# Sheet2.net
KiCad netlist of a schematic drawn in Altium Designer
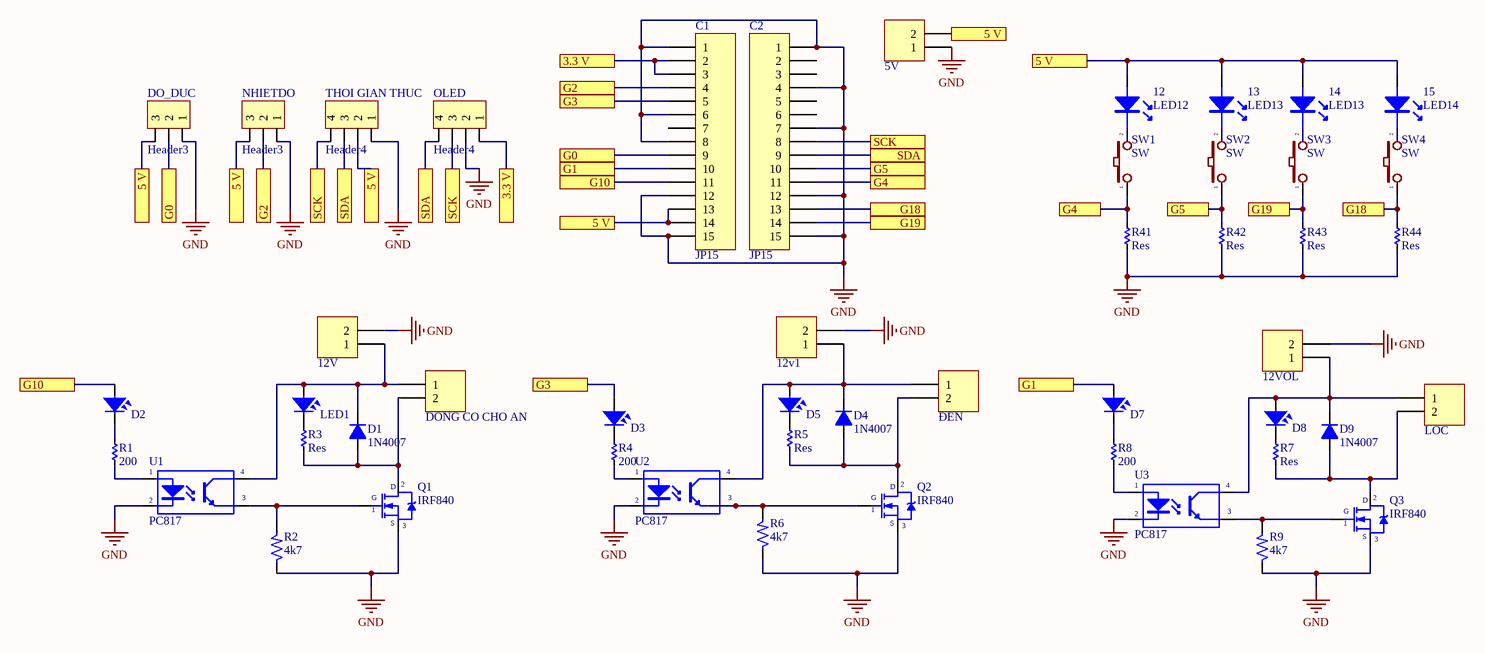
[diagram p0: Sheet2.SchDoc]

(export (version "E")
  (design (tool "Eeschema 10.0.6"))
  (components
    (comp (ref "5V")
      (value "Header 2_1")
      (footprint "HED2")
      (description "Header, 2-Pin")
      (fields (field (name "MANUFACTURER") "Generic Components"))
      (libsource (lib "syhaunguyen__1") (part "Header 2_1"))
    )
    (comp (ref "12") (value "LED12") (footprint "CAP10UF") (libsource (lib "minhha") (part "LED")))
    (comp (ref "12V")
      (value "Header 2_1")
      (footprint "HED2")
      (description "Header, 2-Pin")
      (fields (field (name "MANUFACTURER") "Generic Components"))
      (libsource (lib "syhaunguyen__1") (part "Header 2_1"))
    )
    (comp (ref "12v1")
      (value "Header 2_1")
      (footprint "HED2")
      (description "Header, 2-Pin")
      (fields (field (name "MANUFACTURER") "Generic Components"))
      (libsource (lib "syhaunguyen__1") (part "Header 2_1"))
    )
    (comp (ref "12VOL")
      (value "Header 2_1")
      (footprint "HED2")
      (description "Header, 2-Pin")
      (fields (field (name "MANUFACTURER") "Generic Components"))
      (libsource (lib "syhaunguyen__1") (part "Header 2_1"))
    )
    (comp (ref "13") (value "LED13") (footprint "CAP10UF") (libsource (lib "minhha") (part "LED")))
    (comp (ref "14") (value "LED13") (footprint "CAP10UF") (libsource (lib "minhha") (part "LED")))
    (comp (ref "15") (value "LED14") (footprint "CAP10UF") (libsource (lib "minhha") (part "LED")))
    (comp (ref "C1")
      (value "JP15")
      (footprint "JP15-C1T")
      (description "WR-PHD 2.54 mm Angled Socket Header")
      (fields
        (field (name "MANUFACTURER") "Würth Elektronik eiSos GmbH")
        (field (name "PARTNO") "613015143121")
        (field (name "CREATED BY") "Karrer Zheng")
      )
      (libsource (lib "") (part "JP15_1"))
    )
    (comp (ref "C2")
      (value "JP15")
      (footprint "JP15-C1T")
      (description "WR-PHD 2.54 mm Angled Socket Header")
      (fields
        (field (name "MANUFACTURER") "Würth Elektronik eiSos GmbH")
        (field (name "PARTNO") "613015143121")
        (field (name "CREATED BY") "Karrer Zheng")
      )
      (libsource (lib "Library1") (part "JP15"))
    )
    (comp (ref "D1")
      (value "1N4007")
      (footprint "D1A")
      (description "Diode 1A")
      (libsource (lib "minhha") (part "D1A"))
    )
    (comp (ref "D2")
      (value "LED")
      (footprint "LED-3")
      (description "LED Single colour Green and Red")
      (libsource (lib "Altium_Devzone") (part "LED"))
    )
    (comp (ref "D3")
      (value "LED")
      (footprint "LED-3")
      (description "LED Single colour Green and Red")
      (libsource (lib "Altium_Devzone") (part "LED"))
    )
    (comp (ref "D4")
      (value "1N4007")
      (footprint "D1A")
      (description "Diode 1A")
      (libsource (lib "minhha") (part "D1A"))
    )
    (comp (ref "D5")
      (value "LED")
      (footprint "LED-3MM-YELLOW")
      (description "LED Single colour Green and Red")
      (libsource (lib "Library1") (part "LED"))
    )
    (comp (ref "D7")
      (value "LED")
      (footprint "LED-3")
      (description "LED Single colour Green and Red")
      (libsource (lib "Altium_Devzone") (part "LED"))
    )
    (comp (ref "D8")
      (value "LED")
      (footprint "LED-3MM-YELLOW")
      (description "LED Single colour Green and Red")
      (libsource (lib "Library1") (part "LED"))
    )
    (comp (ref "D9")
      (value "1N4007")
      (footprint "D1A")
      (description "Diode 1A")
      (libsource (lib "minhha") (part "D1A"))
    )
    (comp (ref "DONG CO CHO AN")
      (value "Header 2_1")
      (footprint "HED2")
      (description "Header, 2-Pin")
      (fields (field (name "MANUFACTURER") "Generic Components"))
      (libsource (lib "") (part "Header 2_1_1"))
    )
    (comp (ref "DO_DUC")
      (value "Header3")
      (footprint "Header3")
      (description "Header IDC, 3 x 1 Pin Vertical 2.54mm Pitch (Non-Boxed, Male)")
      (fields
        (field (name "MANUFACTURER") "Würth Elektronik eiSos GmbH")
        (field (name "PARTNO") "613002143121")
        (field (name "CREATED BY") "Karrer Zheng")
      )
      (libsource (lib "Library1") (part "Header3"))
    )
    (comp (ref "LED1")
      (value "LED")
      (footprint "LED-3MM-YELLOW")
      (description "LED Single colour Green and Red")
      (libsource (lib "Library1") (part "LED"))
    )
    (comp (ref "LOC")
      (value "Header 2_1")
      (footprint "HED2")
      (description "Header, 2-Pin")
      (fields (field (name "MANUFACTURER") "Generic Components"))
      (libsource (lib "") (part "Header 2_1_1"))
    )
    (comp (ref "NHIETDO")
      (value "Header3")
      (footprint "Header3")
      (description "Header IDC, 3 x 1 Pin Vertical 2.54mm Pitch (Non-Boxed, Male)")
      (fields
        (field (name "MANUFACTURER") "Würth Elektronik eiSos GmbH")
        (field (name "PARTNO") "613002143121")
        (field (name "CREATED BY") "Karrer Zheng")
      )
      (libsource (lib "Library1") (part "Header3"))
    )
    (comp (ref "OLED")
      (value "Header4")
      (footprint "Header4")
      (description "Header IDC, 4 x 1 Pin Vertical 2.54mm Pitch (Non-Boxed, Male)")
      (fields
        (field (name "MANUFACTURER") "Würth Elektronik eiSos GmbH")
        (field (name "PARTNO") "613002143121")
        (field (name "CREATED BY") "Karrer Zheng")
      )
      (libsource (lib "Library1") (part "Header4"))
    )
    (comp (ref "Q1")
      (value "IRF840")
      (footprint "TO220H1")
      (description "MOSFET N - CHANNEL 500V - 0.75 - 8A - TO-220")
      (libsource (lib "Library1") (part "IRF840"))
    )
    (comp (ref "Q2")
      (value "IRF840")
      (footprint "TO220H1")
      (description "MOSFET N - CHANNEL 500V - 0.75 - 8A - TO-220")
      (libsource (lib "Library1") (part "IRF840"))
    )
    (comp (ref "Q3")
      (value "IRF840")
      (footprint "TO220H1")
      (description "MOSFET N - CHANNEL 500V - 0.75 - 8A - TO-220")
      (libsource (lib "Library1") (part "IRF840"))
    )
    (comp (ref "R1")
      (value "200")
      (footprint "RES-1/2W")
      (description "Res")
      (fields
        (field (name "MANUFACTURER") "Generic Components")
        (field (name "PUBLISHER") "Altium Hobart Technology Centre")
      )
      (libsource (lib "Library1") (part "Res"))
    )
    (comp (ref "R2")
      (value "4k7")
      (footprint "DIEN TRO 1/4 W")
      (description "Resistor 1/4W")
      (libsource (lib "minhha") (part "Res"))
    )
    (comp (ref "R3")
      (value "Res")
      (footprint "RES-1/2W")
      (fields
        (field (name "MANUFACTURER") "Generic Components")
        (field (name "PUBLISHER") "Altium Hobart Technology Centre")
      )
      (libsource (lib "Library1") (part "Res"))
    )
    (comp (ref "R4")
      (value "200")
      (footprint "RES-1/2W")
      (description "Res")
      (fields
        (field (name "MANUFACTURER") "Generic Components")
        (field (name "PUBLISHER") "Altium Hobart Technology Centre")
      )
      (libsource (lib "Library1") (part "Res"))
    )
    (comp (ref "R5")
      (value "Res")
      (footprint "RES-1/2W")
      (fields
        (field (name "MANUFACTURER") "Generic Components")
        (field (name "PUBLISHER") "Altium Hobart Technology Centre")
      )
      (libsource (lib "Library1") (part "Res"))
    )
    (comp (ref "R6")
      (value "4k7")
      (footprint "DIEN TRO 1/4 W")
      (description "Resistor 1/4W")
      (libsource (lib "minhha") (part "Res"))
    )
    (comp (ref "R7")
      (value "Res")
      (footprint "RES-1/2W")
      (fields
        (field (name "MANUFACTURER") "Generic Components")
        (field (name "PUBLISHER") "Altium Hobart Technology Centre")
      )
      (libsource (lib "Library1") (part "Res"))
    )
    (comp (ref "R8")
      (value "200")
      (footprint "RES-1/2W")
      (description "Res")
      (fields
        (field (name "MANUFACTURER") "Generic Components")
        (field (name "PUBLISHER") "Altium Hobart Technology Centre")
      )
      (libsource (lib "Library1") (part "Res"))
    )
    (comp (ref "R9")
      (value "4k7")
      (footprint "DIEN TRO 1/4 W")
      (description "Resistor 1/4W")
      (libsource (lib "minhha") (part "Res"))
    )
    (comp (ref "R41")
      (value "Res")
      (footprint "RES-1/2W")
      (fields
        (field (name "MANUFACTURER") "Generic Components")
        (field (name "PUBLISHER") "Altium Hobart Technology Centre")
      )
      (libsource (lib "Library1") (part "Res"))
    )
    (comp (ref "R42")
      (value "Res")
      (footprint "RES-1/2W")
      (fields
        (field (name "MANUFACTURER") "Generic Components")
        (field (name "PUBLISHER") "Altium Hobart Technology Centre")
      )
      (libsource (lib "Library1") (part "Res"))
    )
    (comp (ref "R43")
      (value "Res")
      (footprint "RES-1/2W")
      (fields
        (field (name "MANUFACTURER") "Generic Components")
        (field (name "PUBLISHER") "Altium Hobart Technology Centre")
      )
      (libsource (lib "Library1") (part "Res"))
    )
    (comp (ref "R44")
      (value "Res")
      (footprint "RES-1/2W")
      (fields
        (field (name "MANUFACTURER") "Generic Components")
        (field (name "PUBLISHER") "Altium Hobart Technology Centre")
      )
      (libsource (lib "Library1") (part "Res"))
    )
    (comp (ref "SW1")
      (value "SW")
      (footprint "SW2")
      (description "Switch button 2 pin")
      (libsource (lib "syhaunguyen__1") (part "SW2"))
    )
    (comp (ref "SW2")
      (value "SW")
      (footprint "SW2")
      (description "Switch button 2 pin")
      (libsource (lib "syhaunguyen__1") (part "SW2"))
    )
    (comp (ref "SW3")
      (value "SW")
      (footprint "SW2")
      (description "Switch button 2 pin")
      (libsource (lib "syhaunguyen__1") (part "SW2"))
    )
    (comp (ref "SW4")
      (value "SW")
      (footprint "SW2")
      (description "Switch button 2 pin")
      (libsource (lib "syhaunguyen__1") (part "SW2"))
    )
    (comp (ref "THOI GIAN THUC")
      (value "Header4")
      (footprint "Header4")
      (description "Header IDC, 4 x 1 Pin Vertical 2.54mm Pitch (Non-Boxed, Male)")
      (fields
        (field (name "MANUFACTURER") "Würth Elektronik eiSos GmbH")
        (field (name "PARTNO") "613002143121")
        (field (name "CREATED BY") "Karrer Zheng")
      )
      (libsource (lib "Library1") (part "Header4"))
    )
    (comp (ref "U1")
      (value "PC817")
      (footprint "DIP4")
      (description "Single Opto")
      (libsource (lib "Library1") (part "PC817"))
    )
    (comp (ref "U2")
      (value "PC817")
      (footprint "DIP4")
      (description "Single Opto")
      (libsource (lib "Library1") (part "PC817"))
    )
    (comp (ref "U3")
      (value "PC817")
      (footprint "DIP4")
      (description "Single Opto")
      (libsource (lib "Library1") (part "PC817"))
    )
    (comp (ref "ĐEN")
      (value "Header 2_1")
      (footprint "HED2")
      (description "Header, 2-Pin")
      (fields (field (name "MANUFACTURER") "Generic Components"))
      (libsource (lib "") (part "Header 2_1_1"))
    )
  )
  (nets
    (net (code "1") (name "/3.3 V") (class "Default")
      (node (ref "C1") (pin "2") (pinfunction "2_2") (pintype "passive"))
      (node (ref "C1") (pin "3") (pinfunction "3_3") (pintype "passive"))
      (node (ref "OLED") (pin "1") (pinfunction "1_1") (pintype "passive"))
    )
    (net (code "2") (name "/5 V") (class "Default")
      (node (ref "12") (pin "1") (pinfunction "1_1") (pintype "passive"))
      (node (ref "13") (pin "1") (pinfunction "1_1") (pintype "passive"))
      (node (ref "14") (pin "1") (pinfunction "1_1") (pintype "passive"))
      (node (ref "15") (pin "1") (pinfunction "1_1") (pintype "passive"))
      (node (ref "5V") (pin "2") (pinfunction "2_2") (pintype "passive"))
      (node (ref "C1") (pin "13") (pinfunction "13_13") (pintype "passive"))
      (node (ref "C1") (pin "14") (pinfunction "14_14") (pintype "passive"))
      (node (ref "DO_DUC") (pin "3") (pinfunction "3_3") (pintype "passive"))
      (node (ref "NHIETDO") (pin "3") (pinfunction "3_3") (pintype "passive"))
      (node (ref "THOI GIAN THUC") (pin "2") (pinfunction "2_2") (pintype "passive"))
    )
    (net (code "3") (name "/G0") (class "Default")
      (node (ref "C1") (pin "9") (pinfunction "9_9") (pintype "passive"))
      (node (ref "DO_DUC") (pin "2") (pinfunction "2_2") (pintype "passive"))
    )
    (net (code "4") (name "/G1") (class "Default")
      (node (ref "C1") (pin "10") (pinfunction "10_10") (pintype "passive"))
      (node (ref "D7") (pin "1") (pinfunction "1_1") (pintype "passive"))
    )
    (net (code "5") (name "/G2") (class "Default")
      (node (ref "C1") (pin "4") (pinfunction "4_4") (pintype "passive"))
      (node (ref "NHIETDO") (pin "2") (pinfunction "2_2") (pintype "passive"))
    )
    (net (code "6") (name "/G3") (class "Default")
      (node (ref "C1") (pin "5") (pinfunction "5_5") (pintype "passive"))
      (node (ref "D3") (pin "1") (pinfunction "1_1") (pintype "passive"))
    )
    (net (code "7") (name "/G4") (class "Default")
      (node (ref "C2") (pin "11") (pinfunction "11_11") (pintype "passive"))
      (node (ref "R41") (pin "1") (pinfunction "1_1") (pintype "passive"))
      (node (ref "SW1") (pin "1") (pinfunction "1_1") (pintype "passive"))
    )
    (net (code "8") (name "/G5") (class "Default")
      (node (ref "C2") (pin "10") (pinfunction "10_10") (pintype "passive"))
      (node (ref "R42") (pin "1") (pinfunction "1_1") (pintype "passive"))
      (node (ref "SW2") (pin "1") (pinfunction "1_1") (pintype "passive"))
    )
    (net (code "9") (name "/G10") (class "Default")
      (node (ref "C1") (pin "11") (pinfunction "11_11") (pintype "passive"))
      (node (ref "D2") (pin "1") (pinfunction "1_1") (pintype "passive"))
    )
    (net (code "10") (name "/G18") (class "Default")
      (node (ref "C2") (pin "13") (pinfunction "13_13") (pintype "passive"))
      (node (ref "R44") (pin "1") (pinfunction "1_1") (pintype "passive"))
      (node (ref "SW4") (pin "1") (pinfunction "1_1") (pintype "passive"))
    )
    (net (code "11") (name "/G19") (class "Default")
      (node (ref "C2") (pin "14") (pinfunction "14_14") (pintype "passive"))
      (node (ref "R43") (pin "1") (pinfunction "1_1") (pintype "passive"))
      (node (ref "SW3") (pin "1") (pinfunction "1_1") (pintype "passive"))
    )
    (net (code "12") (name "/SCK") (class "Default")
      (node (ref "C2") (pin "8") (pinfunction "8_8") (pintype "passive"))
      (node (ref "OLED") (pin "3") (pinfunction "3_3") (pintype "passive"))
      (node (ref "THOI GIAN THUC") (pin "4") (pinfunction "4_4") (pintype "passive"))
    )
    (net (code "13") (name "/SDA") (class "Default")
      (node (ref "C2") (pin "9") (pinfunction "9_9") (pintype "passive"))
      (node (ref "OLED") (pin "4") (pinfunction "4_4") (pintype "passive"))
      (node (ref "THOI GIAN THUC") (pin "3") (pinfunction "3_3") (pintype "passive"))
    )
    (net (code "14") (name "GND") (class "Default")
      (node (ref "12V") (pin "2") (pinfunction "2_2") (pintype "passive"))
      (node (ref "12VOL") (pin "2") (pinfunction "2_2") (pintype "passive"))
      (node (ref "12v1") (pin "2") (pinfunction "2_2") (pintype "passive"))
      (node (ref "5V") (pin "1") (pinfunction "1_1") (pintype "passive"))
      (node (ref "C1") (pin "1") (pinfunction "1_1") (pintype "passive"))
      (node (ref "C1") (pin "12") (pinfunction "12_12") (pintype "passive"))
      (node (ref "C1") (pin "15") (pinfunction "15_15") (pintype "passive"))
      (node (ref "C1") (pin "6") (pinfunction "6_6") (pintype "passive"))
      (node (ref "C1") (pin "8") (pinfunction "8_8") (pintype "passive"))
      (node (ref "C2") (pin "1") (pinfunction "1_1") (pintype "passive"))
      (node (ref "C2") (pin "12") (pinfunction "12_12") (pintype "passive"))
      (node (ref "C2") (pin "15") (pinfunction "15_15") (pintype "passive"))
      (node (ref "C2") (pin "4") (pinfunction "4_4") (pintype "passive"))
      (node (ref "C2") (pin "7") (pinfunction "7_7") (pintype "passive"))
      (node (ref "DO_DUC") (pin "1") (pinfunction "1_1") (pintype "passive"))
      (node (ref "NHIETDO") (pin "1") (pinfunction "1_1") (pintype "passive"))
      (node (ref "OLED") (pin "2") (pinfunction "2_2") (pintype "passive"))
      (node (ref "Q1") (pin "3") (pinfunction "S_3") (pintype "passive"))
      (node (ref "Q2") (pin "3") (pinfunction "S_3") (pintype "passive"))
      (node (ref "Q3") (pin "3") (pinfunction "S_3") (pintype "passive"))
      (node (ref "R2") (pin "1") (pinfunction "1_1") (pintype "passive"))
      (node (ref "R41") (pin "2") (pinfunction "2_2") (pintype "passive"))
      (node (ref "R42") (pin "2") (pinfunction "2_2") (pintype "passive"))
      (node (ref "R43") (pin "2") (pinfunction "2_2") (pintype "passive"))
      (node (ref "R44") (pin "2") (pinfunction "2_2") (pintype "passive"))
      (node (ref "R6") (pin "1") (pinfunction "1_1") (pintype "passive"))
      (node (ref "R9") (pin "1") (pinfunction "1_1") (pintype "passive"))
      (node (ref "THOI GIAN THUC") (pin "1") (pinfunction "1_1") (pintype "passive"))
      (node (ref "U1") (pin "2") (pinfunction "K_2") (pintype "passive"))
      (node (ref "U2") (pin "2") (pinfunction "K_2") (pintype "passive"))
      (node (ref "U3") (pin "2") (pinfunction "K_2") (pintype "passive"))
    )
    (net (code "15") (name "Net-(12-Pad2)") (class "Default")
      (node (ref "12") (pin "2") (pinfunction "2_2") (pintype "passive"))
      (node (ref "SW1") (pin "2") (pinfunction "2_2") (pintype "passive"))
    )
    (net (code "16") (name "Net-(13-Pad2)") (class "Default")
      (node (ref "13") (pin "2") (pinfunction "2_2") (pintype "passive"))
      (node (ref "SW2") (pin "2") (pinfunction "2_2") (pintype "passive"))
    )
    (net (code "17") (name "Net-(14-Pad2)") (class "Default")
      (node (ref "14") (pin "2") (pinfunction "2_2") (pintype "passive"))
      (node (ref "SW3") (pin "2") (pinfunction "2_2") (pintype "passive"))
    )
    (net (code "18") (name "Net-(15-Pad2)") (class "Default")
      (node (ref "15") (pin "2") (pinfunction "2_2") (pintype "passive"))
      (node (ref "SW4") (pin "2") (pinfunction "2_2") (pintype "passive"))
    )
    (net (code "19") (name "Net-(D1-A)") (class "Default")
      (node (ref "D1") (pin "1") (pinfunction "A_1") (pintype "passive"))
      (node (ref "DONG CO CHO AN") (pin "2") (pinfunction "2_2") (pintype "passive"))
      (node (ref "Q1") (pin "2") (pinfunction "D_2") (pintype "passive"))
      (node (ref "R3") (pin "2") (pinfunction "2_2") (pintype "passive"))
    )
    (net (code "20") (name "Net-(D1-K)") (class "Default")
      (node (ref "12V") (pin "1") (pinfunction "1_1") (pintype "passive"))
      (node (ref "D1") (pin "2") (pinfunction "K_2") (pintype "passive"))
      (node (ref "DONG CO CHO AN") (pin "1") (pinfunction "1_1") (pintype "passive"))
      (node (ref "LED1") (pin "1") (pinfunction "1_1") (pintype "passive"))
      (node (ref "U1") (pin "4") (pinfunction "C_4") (pintype "passive"))
    )
    (net (code "21") (name "Net-(D2-Pad2)") (class "Default")
      (node (ref "D2") (pin "2") (pinfunction "2_2") (pintype "passive"))
      (node (ref "R1") (pin "1") (pinfunction "1_1") (pintype "passive"))
    )
    (net (code "22") (name "Net-(D3-Pad2)") (class "Default")
      (node (ref "D3") (pin "2") (pinfunction "2_2") (pintype "passive"))
      (node (ref "R4") (pin "1") (pinfunction "1_1") (pintype "passive"))
    )
    (net (code "23") (name "Net-(D4-A)") (class "Default")
      (node (ref "D4") (pin "1") (pinfunction "A_1") (pintype "passive"))
      (node (ref "Q2") (pin "2") (pinfunction "D_2") (pintype "passive"))
      (node (ref "R5") (pin "2") (pinfunction "2_2") (pintype "passive"))
      (node (ref "ĐEN") (pin "2") (pinfunction "2_2") (pintype "passive"))
    )
    (net (code "24") (name "Net-(D4-K)") (class "Default")
      (node (ref "12v1") (pin "1") (pinfunction "1_1") (pintype "passive"))
      (node (ref "D4") (pin "2") (pinfunction "K_2") (pintype "passive"))
      (node (ref "D5") (pin "1") (pinfunction "1_1") (pintype "passive"))
      (node (ref "U2") (pin "4") (pinfunction "C_4") (pintype "passive"))
      (node (ref "ĐEN") (pin "1") (pinfunction "1_1") (pintype "passive"))
    )
    (net (code "25") (name "Net-(D5-Pad2)") (class "Default")
      (node (ref "D5") (pin "2") (pinfunction "2_2") (pintype "passive"))
      (node (ref "R5") (pin "1") (pinfunction "1_1") (pintype "passive"))
    )
    (net (code "26") (name "Net-(D7-Pad2)") (class "Default")
      (node (ref "D7") (pin "2") (pinfunction "2_2") (pintype "passive"))
      (node (ref "R8") (pin "1") (pinfunction "1_1") (pintype "passive"))
    )
    (net (code "27") (name "Net-(D8-Pad2)") (class "Default")
      (node (ref "D8") (pin "2") (pinfunction "2_2") (pintype "passive"))
      (node (ref "R7") (pin "1") (pinfunction "1_1") (pintype "passive"))
    )
    (net (code "28") (name "Net-(D9-A)") (class "Default")
      (node (ref "D9") (pin "1") (pinfunction "A_1") (pintype "passive"))
      (node (ref "LOC") (pin "2") (pinfunction "2_2") (pintype "passive"))
      (node (ref "Q3") (pin "2") (pinfunction "D_2") (pintype "passive"))
      (node (ref "R7") (pin "2") (pinfunction "2_2") (pintype "passive"))
    )
    (net (code "29") (name "Net-(D9-K)") (class "Default")
      (node (ref "12VOL") (pin "1") (pinfunction "1_1") (pintype "passive"))
      (node (ref "D8") (pin "1") (pinfunction "1_1") (pintype "passive"))
      (node (ref "D9") (pin "2") (pinfunction "K_2") (pintype "passive"))
      (node (ref "LOC") (pin "1") (pinfunction "1_1") (pintype "passive"))
      (node (ref "U3") (pin "4") (pinfunction "C_4") (pintype "passive"))
    )
    (net (code "30") (name "Net-(LED1-Pad2)") (class "Default")
      (node (ref "LED1") (pin "2") (pinfunction "2_2") (pintype "passive"))
      (node (ref "R3") (pin "1") (pinfunction "1_1") (pintype "passive"))
    )
    (net (code "31") (name "Net-(Q1-G)") (class "Default")
      (node (ref "Q1") (pin "1") (pinfunction "G_1") (pintype "passive"))
      (node (ref "R2") (pin "2") (pinfunction "2_2") (pintype "passive"))
      (node (ref "U1") (pin "3") (pinfunction "E_3") (pintype "passive"))
    )
    (net (code "32") (name "Net-(Q2-G)") (class "Default")
      (node (ref "Q2") (pin "1") (pinfunction "G_1") (pintype "passive"))
      (node (ref "R6") (pin "2") (pinfunction "2_2") (pintype "passive"))
      (node (ref "U2") (pin "3") (pinfunction "E_3") (pintype "passive"))
    )
    (net (code "33") (name "Net-(Q3-G)") (class "Default")
      (node (ref "Q3") (pin "1") (pinfunction "G_1") (pintype "passive"))
      (node (ref "R9") (pin "2") (pinfunction "2_2") (pintype "passive"))
      (node (ref "U3") (pin "3") (pinfunction "E_3") (pintype "passive"))
    )
    (net (code "34") (name "Net-(U1-A)") (class "Default")
      (node (ref "R1") (pin "2") (pinfunction "2_2") (pintype "passive"))
      (node (ref "U1") (pin "1") (pinfunction "A_1") (pintype "passive"))
    )
    (net (code "35") (name "Net-(U2-A)") (class "Default")
      (node (ref "R4") (pin "2") (pinfunction "2_2") (pintype "passive"))
      (node (ref "U2") (pin "1") (pinfunction "A_1") (pintype "passive"))
    )
    (net (code "36") (name "Net-(U3-A)") (class "Default")
      (node (ref "R8") (pin "2") (pinfunction "2_2") (pintype "passive"))
      (node (ref "U3") (pin "1") (pinfunction "A_1") (pintype "passive"))
    )
    (net (code "37") (name "unconnected-(C1-Pad7)") (class "Default")
      (node (ref "C1") (pin "7") (pinfunction "7_7") (pintype "passive"))
    )
    (net (code "38") (name "unconnected-(C2-Pad2)") (class "Default")
      (node (ref "C2") (pin "2") (pinfunction "2_2") (pintype "passive"))
    )
    (net (code "39") (name "unconnected-(C2-Pad3)") (class "Default")
      (node (ref "C2") (pin "3") (pinfunction "3_3") (pintype "passive"))
    )
    (net (code "40") (name "unconnected-(C2-Pad5)") (class "Default")
      (node (ref "C2") (pin "5") (pinfunction "5_5") (pintype "passive"))
    )
    (net (code "41") (name "unconnected-(C2-Pad6)") (class "Default")
      (node (ref "C2") (pin "6") (pinfunction "6_6") (pintype "passive"))
    )
  )
)
